# 7_MINIPCIE.net
KiCad netlist of a schematic drawn in Altium Designer
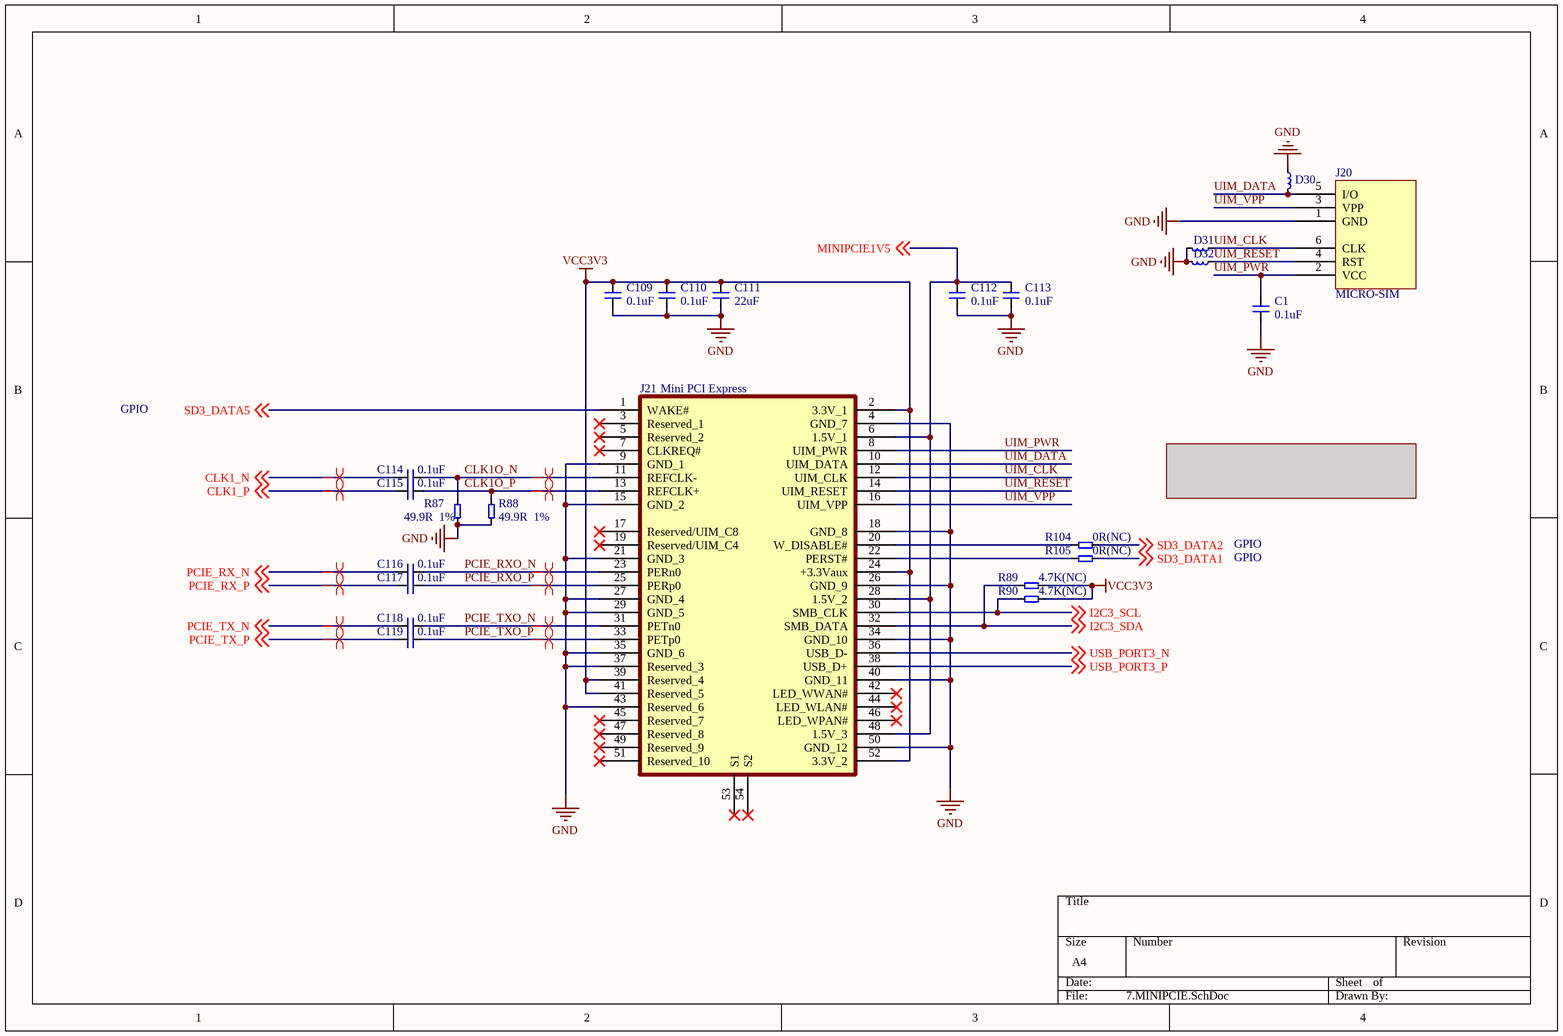
[diagram p0: 7.MINIPCIE.SchDoc]

(export (version "E")
  (design (tool "Eeschema 10.0.6"))
  (components
    (comp (ref "C1")
      (value "0.1uF")
      (footprint "0603C")
      (description "电容")
      (libsource (lib "LDT-SCH") (part "电容"))
    )
    (comp (ref "C109")
      (value "0.1uF")
      (footprint "0603C")
      (description "电容")
      (libsource (lib "LDT-SCH") (part "电容"))
    )
    (comp (ref "C110")
      (value "0.1uF")
      (footprint "0603C")
      (description "电容")
      (libsource (lib "LDT-SCH") (part "电容"))
    )
    (comp (ref "C111")
      (value "22uF")
      (footprint "0603C")
      (description "电容")
      (libsource (lib "LDT-SCH") (part "电容"))
    )
    (comp (ref "C112")
      (value "0.1uF")
      (footprint "0603C")
      (description "电容")
      (libsource (lib "LDT-SCH") (part "电容"))
    )
    (comp (ref "C113")
      (value "0.1uF")
      (footprint "0603C")
      (description "电容")
      (libsource (lib "LDT-SCH") (part "电容"))
    )
    (comp (ref "C114")
      (value "0.1uF")
      (footprint "0603C")
      (description "电容")
      (libsource (lib "LDT-SCH") (part "电容"))
    )
    (comp (ref "C115")
      (value "0.1uF")
      (footprint "0603C")
      (description "电容")
      (libsource (lib "LDT-SCH") (part "电容"))
    )
    (comp (ref "C116")
      (value "0.1uF")
      (footprint "0603C")
      (description "电容")
      (libsource (lib "LDT-SCH") (part "电容"))
    )
    (comp (ref "C117")
      (value "0.1uF")
      (footprint "0603C")
      (description "电容")
      (libsource (lib "LDT-SCH") (part "电容"))
    )
    (comp (ref "C118")
      (value "0.1uF")
      (footprint "0603C")
      (description "电容")
      (libsource (lib "LDT-SCH") (part "电容"))
    )
    (comp (ref "C119")
      (value "0.1uF")
      (footprint "0603C")
      (description "电容")
      (libsource (lib "LDT-SCH") (part "电容"))
    )
    (comp (ref "D30") (value "ESD") (footprint "0603L") (libsource (lib "LDT-SCH") (part "电感")))
    (comp (ref "D31") (value "ESD") (footprint "0603L") (libsource (lib "LDT-SCH") (part "电感")))
    (comp (ref "D32") (value "ESD") (footprint "0603L") (libsource (lib "LDT-SCH") (part "电感")))
    (comp (ref "J20")
      (value "MICRO-SIM")
      (footprint "MACRO-SIM")
      (libsource (lib "LDT-SCH") (part "MICRO-SIM"))
    )
    (comp (ref "J21")
      (value "Mini PCI Express")
      (footprint "Tank:MINI-PCIE")
      (description "MPC24-52K3311")
      (libsource (lib "LDT-SCH") (part "MINIPCIE"))
    )
    (comp (ref "R87")
      (value "49.9R  1%")
      (footprint "0603R")
      (description "电阻")
      (libsource (lib "LDT-SCH") (part "电阻"))
    )
    (comp (ref "R88")
      (value "49.9R  1%")
      (footprint "0603R")
      (description "电阻")
      (libsource (lib "LDT-SCH") (part "电阻"))
    )
    (comp (ref "R89")
      (value "4.7K(NC)")
      (footprint "0603R")
      (description "电阻")
      (libsource (lib "LDT-SCH") (part "电阻"))
    )
    (comp (ref "R90")
      (value "4.7K(NC)")
      (footprint "0603R")
      (description "电阻")
      (libsource (lib "LDT-SCH") (part "电阻"))
    )
    (comp (ref "R104")
      (value "0R(NC)")
      (footprint "0603R")
      (description "电阻")
      (libsource (lib "LDT-SCH") (part "电阻"))
    )
    (comp (ref "R105")
      (value "0R(NC)")
      (footprint "0603R")
      (description "电阻")
      (libsource (lib "LDT-SCH") (part "电阻"))
    )
  )
  (nets
    (net (code "1") (name "/CLK1O_N") (class "Default")
      (node (ref "C114") (pin "2") (pintype "passive"))
      (node (ref "J21") (pin "11") (pinfunction "REFCLK-_11") (pintype "passive"))
      (node (ref "R87") (pin "2") (pintype "passive"))
    )
    (net (code "2") (name "/CLK1O_P") (class "Default")
      (node (ref "C115") (pin "2") (pintype "passive"))
      (node (ref "J21") (pin "13") (pinfunction "REFCLK+_13") (pintype "passive"))
      (node (ref "R88") (pin "2") (pintype "passive"))
    )
    (net (code "3") (name "/PCIE_RXO_N") (class "Default")
      (node (ref "C116") (pin "2") (pintype "passive"))
      (node (ref "J21") (pin "23") (pinfunction "PERn0_23") (pintype "passive"))
    )
    (net (code "4") (name "/PCIE_RXO_P") (class "Default")
      (node (ref "C117") (pin "2") (pintype "passive"))
      (node (ref "J21") (pin "25") (pinfunction "PERp0_25") (pintype "passive"))
    )
    (net (code "5") (name "/PCIE_TXO_N") (class "Default")
      (node (ref "C118") (pin "2") (pintype "passive"))
      (node (ref "J21") (pin "31") (pinfunction "PETn0_31") (pintype "passive"))
    )
    (net (code "6") (name "/PCIE_TXO_P") (class "Default")
      (node (ref "C119") (pin "2") (pintype "passive"))
      (node (ref "J21") (pin "33") (pinfunction "PETp0_33") (pintype "passive"))
    )
    (net (code "7") (name "/UIM_CLK") (class "Default")
      (node (ref "D31") (pin "1") (pintype "passive"))
      (node (ref "J20") (pin "6") (pinfunction "CLK_6") (pintype "passive"))
      (node (ref "J21") (pin "12") (pinfunction "UIM_CLK_12") (pintype "passive"))
    )
    (net (code "8") (name "/UIM_DATA") (class "Default")
      (node (ref "D30") (pin "2") (pintype "passive"))
      (node (ref "J20") (pin "5") (pinfunction "I/O_5") (pintype "passive"))
      (node (ref "J21") (pin "10") (pinfunction "UIM_DATA_10") (pintype "passive"))
    )
    (net (code "9") (name "/UIM_PWR") (class "Default")
      (node (ref "C1") (pin "1") (pintype "passive"))
      (node (ref "J20") (pin "2") (pinfunction "VCC_2") (pintype "passive"))
      (node (ref "J21") (pin "8") (pinfunction "UIM_PWR_8") (pintype "passive"))
    )
    (net (code "10") (name "/UIM_RESET") (class "Default")
      (node (ref "D32") (pin "1") (pintype "passive"))
      (node (ref "J20") (pin "4") (pinfunction "RST_4") (pintype "passive"))
      (node (ref "J21") (pin "14") (pinfunction "UIM_RESET_14") (pintype "passive"))
    )
    (net (code "11") (name "/UIM_VPP") (class "Default")
      (node (ref "J20") (pin "3") (pinfunction "VPP_3") (pintype "passive"))
      (node (ref "J21") (pin "16") (pinfunction "UIM_VPP_16") (pintype "passive"))
    )
    (net (code "12") (name "CLK1_N") (class "Default") (node (ref "C114") (pin "1") (pintype "passive")))
    (net (code "13") (name "CLK1_P") (class "Default") (node (ref "C115") (pin "1") (pintype "passive")))
    (net (code "14") (name "GND") (class "Default")
      (node (ref "C1") (pin "2") (pintype "passive"))
      (node (ref "C109") (pin "2") (pintype "passive"))
      (node (ref "C110") (pin "2") (pintype "passive"))
      (node (ref "C111") (pin "2") (pintype "passive"))
      (node (ref "C112") (pin "2") (pintype "passive"))
      (node (ref "C113") (pin "2") (pintype "passive"))
      (node (ref "D30") (pin "1") (pintype "passive"))
      (node (ref "D31") (pin "2") (pintype "passive"))
      (node (ref "D32") (pin "2") (pintype "passive"))
      (node (ref "J20") (pin "1") (pinfunction "GND_1") (pintype "passive"))
      (node (ref "J21") (pin "15") (pinfunction "GND_2_15") (pintype "passive"))
      (node (ref "J21") (pin "18") (pinfunction "GND_8_18") (pintype "passive"))
      (node (ref "J21") (pin "21") (pinfunction "GND_3_21") (pintype "passive"))
      (node (ref "J21") (pin "26") (pinfunction "GND_9_26") (pintype "passive"))
      (node (ref "J21") (pin "27") (pinfunction "GND_4_27") (pintype "passive"))
      (node (ref "J21") (pin "29") (pinfunction "GND_5_29") (pintype "passive"))
      (node (ref "J21") (pin "34") (pinfunction "GND_10_34") (pintype "passive"))
      (node (ref "J21") (pin "35") (pinfunction "GND_6_35") (pintype "passive"))
      (node (ref "J21") (pin "37") (pinfunction "Reserved_3_37") (pintype "passive"))
      (node (ref "J21") (pin "4") (pinfunction "GND_7_4") (pintype "passive"))
      (node (ref "J21") (pin "40") (pinfunction "GND_11_40") (pintype "passive"))
      (node (ref "J21") (pin "43") (pinfunction "Reserved_6_43") (pintype "passive"))
      (node (ref "J21") (pin "50") (pinfunction "GND_12_50") (pintype "passive"))
      (node (ref "J21") (pin "9") (pinfunction "GND_1_9") (pintype "passive"))
      (node (ref "R87") (pin "1") (pintype "passive"))
      (node (ref "R88") (pin "1") (pintype "passive"))
    )
    (net (code "15") (name "I2C3_SCL") (class "Default")
      (node (ref "J21") (pin "30") (pinfunction "SMB_CLK_30") (pintype "passive"))
      (node (ref "R90") (pin "2") (pintype "passive"))
    )
    (net (code "16") (name "I2C3_SDA") (class "Default")
      (node (ref "J21") (pin "32") (pinfunction "SMB_DATA_32") (pintype "passive"))
      (node (ref "R89") (pin "2") (pintype "passive"))
    )
    (net (code "17") (name "MINIPCIE1V5") (class "Default")
      (node (ref "C112") (pin "1") (pintype "passive"))
      (node (ref "C113") (pin "1") (pintype "passive"))
      (node (ref "J21") (pin "28") (pinfunction "1.5V_2_28") (pintype "passive"))
      (node (ref "J21") (pin "48") (pinfunction "1.5V_3_48") (pintype "passive"))
      (node (ref "J21") (pin "6") (pinfunction "1.5V_1_6") (pintype "passive"))
    )
    (net (code "18") (name "Net-(J21-PERST#)") (class "Default")
      (node (ref "J21") (pin "22") (pinfunction "PERST#_22") (pintype "passive"))
      (node (ref "R105") (pin "2") (pintype "passive"))
    )
    (net (code "19") (name "Net-(J21-W_DISABLE#)") (class "Default")
      (node (ref "J21") (pin "20") (pinfunction "W_DISABLE#_20") (pintype "passive"))
      (node (ref "R104") (pin "2") (pintype "passive"))
    )
    (net (code "20") (name "PCIE_RX_N") (class "Default") (node (ref "C116") (pin "1") (pintype "passive")))
    (net (code "21") (name "PCIE_RX_P") (class "Default") (node (ref "C117") (pin "1") (pintype "passive")))
    (net (code "22") (name "PCIE_TX_N") (class "Default") (node (ref "C118") (pin "1") (pintype "passive")))
    (net (code "23") (name "PCIE_TX_P") (class "Default") (node (ref "C119") (pin "1") (pintype "passive")))
    (net (code "24") (name "SD3_DATA1") (class "Default") (node (ref "R105") (pin "1") (pintype "passive")))
    (net (code "25") (name "SD3_DATA2") (class "Default") (node (ref "R104") (pin "1") (pintype "passive")))
    (net (code "26") (name "SD3_DATA5") (class "Default")
      (node (ref "J21") (pin "1") (pinfunction "WAKE#_1") (pintype "passive"))
    )
    (net (code "27") (name "USB_PORT3_N") (class "Default")
      (node (ref "J21") (pin "36") (pinfunction "USB_D-_36") (pintype "passive"))
    )
    (net (code "28") (name "USB_PORT3_P") (class "Default")
      (node (ref "J21") (pin "38") (pinfunction "USB_D+_38") (pintype "passive"))
    )
    (net (code "29") (name "VCC3V3") (class "Default")
      (node (ref "C109") (pin "1") (pintype "passive"))
      (node (ref "C110") (pin "1") (pintype "passive"))
      (node (ref "C111") (pin "1") (pintype "passive"))
      (node (ref "J21") (pin "2") (pinfunction "3.3V_1_2") (pintype "passive"))
      (node (ref "J21") (pin "24") (pinfunction "+3.3Vaux_24") (pintype "passive"))
      (node (ref "J21") (pin "39") (pinfunction "Reserved_4_39") (pintype "passive"))
      (node (ref "J21") (pin "41") (pinfunction "Reserved_5_41") (pintype "passive"))
      (node (ref "J21") (pin "52") (pinfunction "3.3V_2_52") (pintype "passive"))
      (node (ref "R89") (pin "1") (pintype "passive"))
      (node (ref "R90") (pin "1") (pintype "passive"))
    )
    (net (code "30") (name "unconnected-(J21-CLKREQ#-Pad7)") (class "Default")
      (node (ref "J21") (pin "7") (pinfunction "CLKREQ#_7") (pintype "passive+no_connect"))
    )
    (net (code "31") (name "unconnected-(J21-LED_WLAN#-Pad44)") (class "Default")
      (node (ref "J21") (pin "44") (pinfunction "LED_WLAN#_44") (pintype "passive+no_connect"))
    )
    (net (code "32") (name "unconnected-(J21-LED_WPAN#-Pad46)") (class "Default")
      (node (ref "J21") (pin "46") (pinfunction "LED_WPAN#_46") (pintype "passive+no_connect"))
    )
    (net (code "33") (name "unconnected-(J21-LED_WWAN#-Pad42)") (class "Default")
      (node (ref "J21") (pin "42") (pinfunction "LED_WWAN#_42") (pintype "passive+no_connect"))
    )
    (net (code "34") (name "unconnected-(J21-Reserved_1-Pad3)") (class "Default")
      (node (ref "J21") (pin "3") (pinfunction "Reserved_1_3") (pintype "passive+no_connect"))
    )
    (net (code "35") (name "unconnected-(J21-Reserved_2-Pad5)") (class "Default")
      (node (ref "J21") (pin "5") (pinfunction "Reserved_2_5") (pintype "passive+no_connect"))
    )
    (net (code "36") (name "unconnected-(J21-Reserved_7-Pad45)") (class "Default")
      (node (ref "J21") (pin "45") (pinfunction "Reserved_7_45") (pintype "passive+no_connect"))
    )
    (net (code "37") (name "unconnected-(J21-Reserved_8-Pad47)") (class "Default")
      (node (ref "J21") (pin "47") (pinfunction "Reserved_8_47") (pintype "passive+no_connect"))
    )
    (net (code "38") (name "unconnected-(J21-Reserved_9-Pad49)") (class "Default")
      (node (ref "J21") (pin "49") (pinfunction "Reserved_9_49") (pintype "passive+no_connect"))
    )
    (net (code "39") (name "unconnected-(J21-Reserved_10-Pad51)") (class "Default")
      (node (ref "J21") (pin "51") (pinfunction "Reserved_10_51") (pintype "passive+no_connect"))
    )
    (net (code "40") (name "unconnected-(J21-Reserved{slash}UIM_C4-Pad19)") (class "Default")
      (node (ref "J21") (pin "19") (pinfunction "Reserved/UIM_C4_19") (pintype "passive+no_connect"))
    )
    (net (code "41") (name "unconnected-(J21-Reserved{slash}UIM_C8-Pad17)") (class "Default")
      (node (ref "J21") (pin "17") (pinfunction "Reserved/UIM_C8_17") (pintype "passive+no_connect"))
    )
    (net (code "42") (name "unconnected-(J21-S1-Pad53)") (class "Default")
      (node (ref "J21") (pin "53") (pinfunction "S1_53") (pintype "passive+no_connect"))
    )
    (net (code "43") (name "unconnected-(J21-S2-Pad54)") (class "Default")
      (node (ref "J21") (pin "54") (pinfunction "S2_54") (pintype "passive+no_connect"))
    )
  )
)
